# 14_Ethernet.net
KiCad netlist of a schematic drawn in Altium Designer
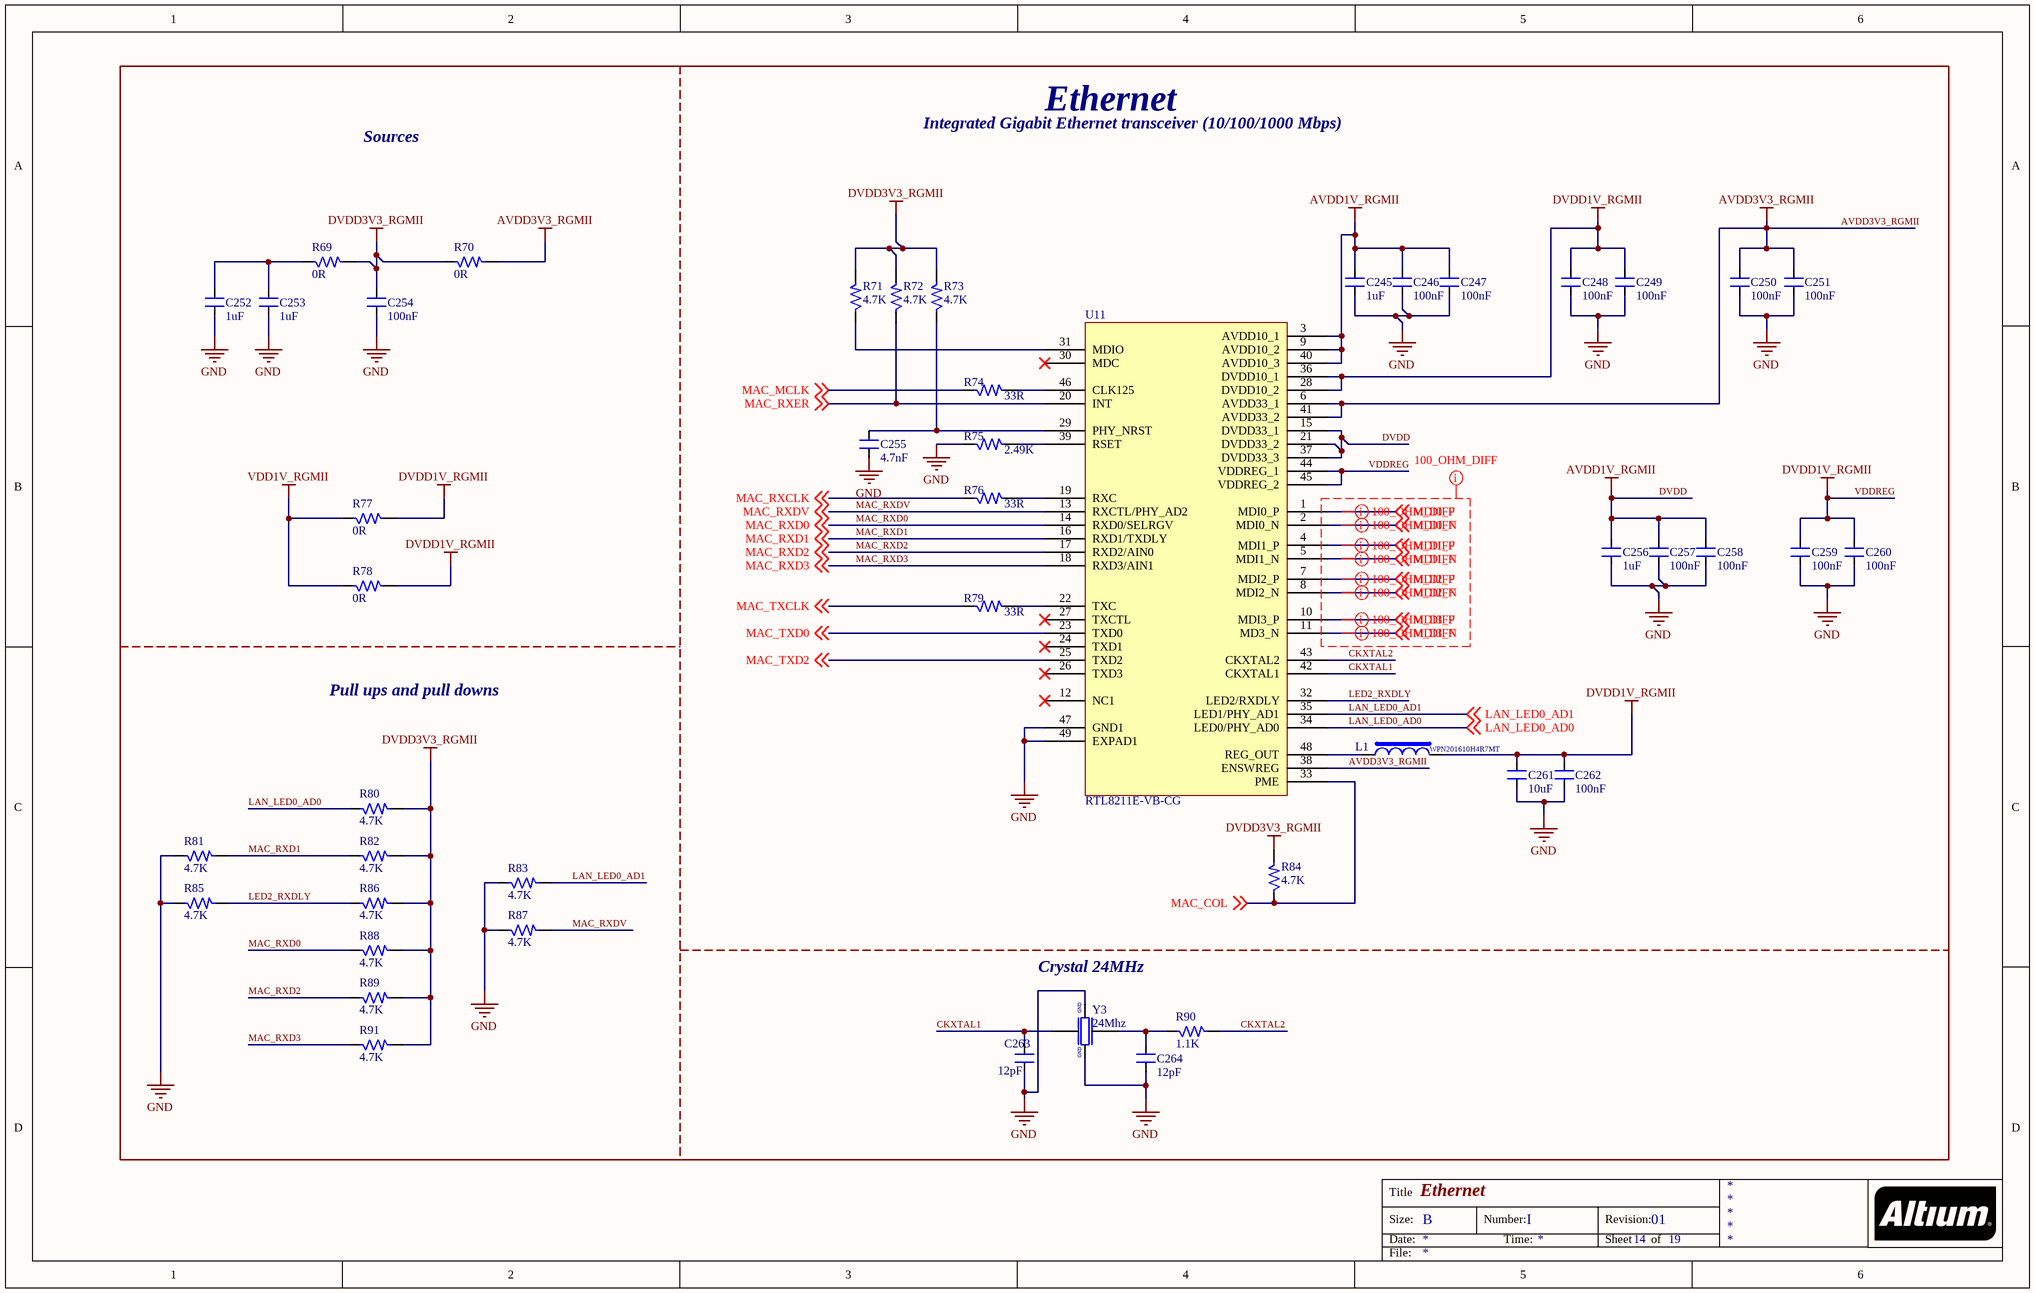
[diagram p0: [14] Ethernet.SchDoc]

(export (version "E")
  (design (tool "Eeschema 10.0.6"))
  (components
    (comp (ref "C245")
      (value "1uF")
      (footprint "CAP_0201")
      (description "1µF ±20% 16V Ceramic Capacitor X5R 0201 (0603 Metric)")
      (fields
        (field (name "MANUFACTURER") "Samsung Electro-Mechanics")
        (field (name "MANUFACTURER PART NUMBER") "CL03A105MO3NRNH")
      )
      (libsource (lib "EsteemPCB_SOM_Course_intlib") (part "CAP_1uF-16V-10%-0201"))
    )
    (comp (ref "C246")
      (value "100nF")
      (footprint "CAP_0201")
      (description "0.1µF ±10% 25V Ceramic Capacitor X5R 0201 (0603 Metric)")
      (fields
        (field (name "MANUFACTURER") "TDK Corporation")
        (field (name "MANUFACTURER PART NUMBER") "C0603X5R1E104K030BB")
      )
      (libsource (lib "EsteemPCB_SOM_Course_intlib") (part "CAP_100nF-25V-10%-0201"))
    )
    (comp (ref "C247")
      (value "100nF")
      (footprint "CAP_0201")
      (description "0.1µF ±10% 25V Ceramic Capacitor X5R 0201 (0603 Metric)")
      (fields
        (field (name "MANUFACTURER") "TDK Corporation")
        (field (name "MANUFACTURER PART NUMBER") "C0603X5R1E104K030BB")
      )
      (libsource (lib "EsteemPCB_SOM_Course_intlib") (part "CAP_100nF-25V-10%-0201"))
    )
    (comp (ref "C248")
      (value "100nF")
      (footprint "CAP_0201")
      (description "0.1µF ±10% 25V Ceramic Capacitor X5R 0201 (0603 Metric)")
      (fields
        (field (name "MANUFACTURER") "TDK Corporation")
        (field (name "MANUFACTURER PART NUMBER") "C0603X5R1E104K030BB")
      )
      (libsource (lib "EsteemPCB_SOM_Course_intlib") (part "CAP_100nF-25V-10%-0201"))
    )
    (comp (ref "C249")
      (value "100nF")
      (footprint "CAP_0201")
      (description "0.1µF ±10% 25V Ceramic Capacitor X5R 0201 (0603 Metric)")
      (fields
        (field (name "MANUFACTURER") "TDK Corporation")
        (field (name "MANUFACTURER PART NUMBER") "C0603X5R1E104K030BB")
      )
      (libsource (lib "EsteemPCB_SOM_Course_intlib") (part "CAP_100nF-25V-10%-0201"))
    )
    (comp (ref "C250")
      (value "100nF")
      (footprint "CAP_0201")
      (description "0.1µF ±10% 25V Ceramic Capacitor X5R 0201 (0603 Metric)")
      (fields
        (field (name "MANUFACTURER") "TDK Corporation")
        (field (name "MANUFACTURER PART NUMBER") "C0603X5R1E104K030BB")
      )
      (libsource (lib "EsteemPCB_SOM_Course_intlib") (part "CAP_100nF-25V-10%-0201"))
    )
    (comp (ref "C251")
      (value "100nF")
      (footprint "CAP_0201")
      (description "0.1µF ±10% 25V Ceramic Capacitor X5R 0201 (0603 Metric)")
      (fields
        (field (name "MANUFACTURER") "TDK Corporation")
        (field (name "MANUFACTURER PART NUMBER") "C0603X5R1E104K030BB")
      )
      (libsource (lib "EsteemPCB_SOM_Course_intlib") (part "CAP_100nF-25V-10%-0201"))
    )
    (comp (ref "C252")
      (value "1uF")
      (footprint "CAP_0402")
      (description "1µF ±10% 16V Ceramic Capacitor X5R 0402 (1005 Metric)")
      (fields
        (field (name "MANUFACTURER") "Knowles Novacap")
        (field (name "MANUFACTURER PART NUMBER") "0402BW105K160YT")
      )
      (libsource (lib "EsteemPCB_SOM_Course_intlib") (part "CAP_1uF-16V-10%-0402"))
    )
    (comp (ref "C253")
      (value "1uF")
      (footprint "CAP_0402")
      (description "1µF ±10% 16V Ceramic Capacitor X5R 0402 (1005 Metric)")
      (fields
        (field (name "MANUFACTURER") "Knowles Novacap")
        (field (name "MANUFACTURER PART NUMBER") "0402BW105K160YT")
      )
      (libsource (lib "EsteemPCB_SOM_Course_intlib") (part "CAP_1uF-16V-10%-0402"))
    )
    (comp (ref "C254")
      (value "100nF")
      (footprint "CAP_0201")
      (description "0.1µF ±10% 25V Ceramic Capacitor X5R 0201 (0603 Metric)")
      (fields
        (field (name "MANUFACTURER") "TDK Corporation")
        (field (name "MANUFACTURER PART NUMBER") "C0603X5R1E104K030BB")
      )
      (libsource (lib "EsteemPCB_SOM_Course_intlib") (part "CAP_100nF-25V-10%-0201"))
    )
    (comp (ref "C255")
      (value "4.7nF")
      (footprint "CAP_0201")
      (description "4700pF ±10% 10V Ceramic Capacitor X7R 0201 (0603 Metric)")
      (fields
        (field (name "MANUFACTURER") "AVX Corporation")
        (field (name "MANUFACTURER PART NUMBER") "0201ZC472KAT2A")
      )
      (libsource (lib "EsteemPCB_SOM_Course_intlib") (part "CAP_4.7nF-10V-10%-0201"))
    )
    (comp (ref "C256")
      (value "1uF")
      (footprint "CAP_0201")
      (description "1µF ±20% 16V Ceramic Capacitor X5R 0201 (0603 Metric)")
      (fields
        (field (name "MANUFACTURER") "Samsung Electro-Mechanics")
        (field (name "MANUFACTURER PART NUMBER") "CL03A105MO3NRNH")
      )
      (libsource (lib "EsteemPCB_SOM_Course_intlib") (part "CAP_1uF-16V-10%-0201"))
    )
    (comp (ref "C257")
      (value "100nF")
      (footprint "CAP_0201")
      (description "0.1µF ±10% 25V Ceramic Capacitor X5R 0201 (0603 Metric)")
      (fields
        (field (name "MANUFACTURER") "TDK Corporation")
        (field (name "MANUFACTURER PART NUMBER") "C0603X5R1E104K030BB")
      )
      (libsource (lib "EsteemPCB_SOM_Course_intlib") (part "CAP_100nF-25V-10%-0201"))
    )
    (comp (ref "C258")
      (value "100nF")
      (footprint "CAP_0201")
      (description "0.1µF ±10% 25V Ceramic Capacitor X5R 0201 (0603 Metric)")
      (fields
        (field (name "MANUFACTURER") "TDK Corporation")
        (field (name "MANUFACTURER PART NUMBER") "C0603X5R1E104K030BB")
      )
      (libsource (lib "EsteemPCB_SOM_Course_intlib") (part "CAP_100nF-25V-10%-0201"))
    )
    (comp (ref "C259")
      (value "100nF")
      (footprint "CAP_0201")
      (description "0.1µF ±10% 25V Ceramic Capacitor X5R 0201 (0603 Metric)")
      (fields
        (field (name "MANUFACTURER") "TDK Corporation")
        (field (name "MANUFACTURER PART NUMBER") "C0603X5R1E104K030BB")
      )
      (libsource (lib "EsteemPCB_SOM_Course_intlib") (part "CAP_100nF-25V-10%-0201"))
    )
    (comp (ref "C260")
      (value "100nF")
      (footprint "CAP_0201")
      (description "0.1µF ±10% 25V Ceramic Capacitor X5R 0201 (0603 Metric)")
      (fields
        (field (name "MANUFACTURER") "TDK Corporation")
        (field (name "MANUFACTURER PART NUMBER") "C0603X5R1E104K030BB")
      )
      (libsource (lib "EsteemPCB_SOM_Course_intlib") (part "CAP_100nF-25V-10%-0201"))
    )
    (comp (ref "C261")
      (value "10uF")
      (footprint "CAP_0402")
      (description "10µF ±20% 10V Ceramic Capacitor X5R 0402 (1005 Metric)")
      (fields
        (field (name "MANUFACTURER PART NUMBER") "CL05A106MP5NUNC")
        (field (name "MANUFACTURER") "Samsung Electro-Mechanics")
      )
      (libsource (lib "EsteemPCB_SOM_Course_intlib") (part "CAP_10uF-10V-20%-0402"))
    )
    (comp (ref "C262")
      (value "100nF")
      (footprint "CAP_0201")
      (description "0.1µF ±10% 25V Ceramic Capacitor X5R 0201 (0603 Metric)")
      (fields
        (field (name "MANUFACTURER") "TDK Corporation")
        (field (name "MANUFACTURER PART NUMBER") "C0603X5R1E104K030BB")
      )
      (libsource (lib "EsteemPCB_SOM_Course_intlib") (part "CAP_100nF-25V-10%-0201"))
    )
    (comp (ref "C263")
      (value "12pF")
      (footprint "CAP_0402")
      (description "12pF ±10% 10V Ceramic Capacitor X8R 0402 (1005 Metric)")
      (fields
        (field (name "MANUFACTURER") "KEMET")
        (field (name "MANUFACTURER PART NUMBER") "C0402C120K8HAC7867")
      )
      (libsource (lib "EsteemPCB_SOM_Course_intlib") (part "CAP_12pF-10V-10%-0402"))
    )
    (comp (ref "C264")
      (value "12pF")
      (footprint "CAP_0402")
      (description "12pF ±10% 10V Ceramic Capacitor X8R 0402 (1005 Metric)")
      (fields
        (field (name "MANUFACTURER") "KEMET")
        (field (name "MANUFACTURER PART NUMBER") "C0402C120K8HAC7867")
      )
      (libsource (lib "EsteemPCB_SOM_Course_intlib") (part "CAP_12pF-10V-10%-0402"))
    )
    (comp (ref "L1")
      (value "WPN201610H4R7MT")
      (footprint "IND_62.9_110X86.6_SMD")
      (description "4.7uH ±20% 900mA 425mΩ SMD,2.0x1.6x1.0mm Power Inductors RoHS")
      (fields (field (name "MANUFACTURER") "Sunlord"))
      (libsource (lib "EsteemPCB_SOM_Course_intlib") (part "IND_4.7uH-0.9A-20%-SMD"))
    )
    (comp (ref "R69")
      (value "0R")
      (footprint "RES_0201")
      (description "0 Ohms Jumper 0.05W, 1/20W Chip Resistor 0201 (0603 Metric) Automotive AEC-Q200 Thick Film")
      (fields
        (field (name "MANUFACTURER") "Bourns Inc.")
        (field (name "MANUFACTURER PART NUMBER") "CR0201AJ/-000GLF")
      )
      (libsource (lib "EsteemPCB_SOM_Course_intlib") (part "RES_0R-0.05W-1%-0201"))
    )
    (comp (ref "R70")
      (value "0R")
      (footprint "RES_0201")
      (description "0 Ohms Jumper 0.05W, 1/20W Chip Resistor 0201 (0603 Metric) Automotive AEC-Q200 Thick Film")
      (fields
        (field (name "MANUFACTURER") "Bourns Inc.")
        (field (name "MANUFACTURER PART NUMBER") "CR0201AJ/-000GLF")
      )
      (libsource (lib "EsteemPCB_SOM_Course_intlib") (part "RES_0R-0.05W-1%-0201"))
    )
    (comp (ref "R71")
      (value "4.7K")
      (footprint "RES_0201")
      (description "4.02 kOhms ±1% 0.05W, 1/20W Chip Resistor 0201 (0603 Metric) Thick Film")
      (fields
        (field (name "MANUFACTURER") "Yageo")
        (field (name "MANUFACTURER PART NUMBER") "RC0201FR-074K02L")
      )
      (libsource (lib "EsteemPCB_SOM_Course_intlib") (part "RES_4.7K-0.1W-1%-0201"))
    )
    (comp (ref "R72")
      (value "4.7K")
      (footprint "RES_0201")
      (description "4.02 kOhms ±1% 0.05W, 1/20W Chip Resistor 0201 (0603 Metric) Thick Film")
      (fields
        (field (name "MANUFACTURER") "Yageo")
        (field (name "MANUFACTURER PART NUMBER") "RC0201FR-074K02L")
      )
      (libsource (lib "EsteemPCB_SOM_Course_intlib") (part "RES_4.7K-0.1W-1%-0201"))
    )
    (comp (ref "R73")
      (value "4.7K")
      (footprint "RES_0201")
      (description "4.02 kOhms ±1% 0.05W, 1/20W Chip Resistor 0201 (0603 Metric) Thick Film")
      (fields
        (field (name "MANUFACTURER") "Yageo")
        (field (name "MANUFACTURER PART NUMBER") "RC0201FR-074K02L")
      )
      (libsource (lib "EsteemPCB_SOM_Course_intlib") (part "RES_4.7K-0.1W-1%-0201"))
    )
    (comp (ref "R74")
      (value "33R")
      (footprint "RES_0201")
      (description "33 Ohms ±1% 0.05W, 1/20W Chip Resistor 0201 (0603 Metric) Thick Film")
      (fields
        (field (name "MANUFACTURER") "Yageo")
        (field (name "MANUFACTURER PART NUMBER") "RC0201FR-0733RL")
      )
      (libsource (lib "EsteemPCB_SOM_Course_intlib") (part "RES_33R-0.05W-1%-0201"))
    )
    (comp (ref "R75")
      (value "2.49K")
      (footprint "RES_0201")
      (description "2.49 kOhms ±1% 0.05W, 1/20W Chip Resistor 0201 (0603 Metric) Automotive AEC-Q200 Thick Film")
      (fields
        (field (name "MANUFACTURER") "Panasonic Electronic Components")
        (field (name "MANUFACTURER PART NUMBER") "ERJ-1GNF2491C")
      )
      (libsource (lib "EsteemPCB_SOM_Course_intlib") (part "RES_2.49K-0.05W-1%-0201"))
    )
    (comp (ref "R76")
      (value "33R")
      (footprint "RES_0201")
      (description "33 Ohms ±1% 0.05W, 1/20W Chip Resistor 0201 (0603 Metric) Thick Film")
      (fields
        (field (name "MANUFACTURER") "Yageo")
        (field (name "MANUFACTURER PART NUMBER") "RC0201FR-0733RL")
      )
      (libsource (lib "EsteemPCB_SOM_Course_intlib") (part "RES_33R-0.05W-1%-0201"))
    )
    (comp (ref "R77")
      (value "0R")
      (footprint "RES_0201")
      (description "0 Ohms Jumper 0.05W, 1/20W Chip Resistor 0201 (0603 Metric) Automotive AEC-Q200 Thick Film")
      (fields
        (field (name "MANUFACTURER") "Bourns Inc.")
        (field (name "MANUFACTURER PART NUMBER") "CR0201AJ/-000GLF")
      )
      (libsource (lib "EsteemPCB_SOM_Course_intlib") (part "RES_0R-0.05W-1%-0201"))
    )
    (comp (ref "R78")
      (value "0R")
      (footprint "RES_0201")
      (description "0 Ohms Jumper 0.05W, 1/20W Chip Resistor 0201 (0603 Metric) Automotive AEC-Q200 Thick Film")
      (fields
        (field (name "MANUFACTURER") "Bourns Inc.")
        (field (name "MANUFACTURER PART NUMBER") "CR0201AJ/-000GLF")
      )
      (libsource (lib "EsteemPCB_SOM_Course_intlib") (part "RES_0R-0.05W-1%-0201"))
    )
    (comp (ref "R79")
      (value "33R")
      (footprint "RES_0201")
      (description "33 Ohms ±1% 0.05W, 1/20W Chip Resistor 0201 (0603 Metric) Thick Film")
      (fields
        (field (name "MANUFACTURER") "Yageo")
        (field (name "MANUFACTURER PART NUMBER") "RC0201FR-0733RL")
      )
      (libsource (lib "EsteemPCB_SOM_Course_intlib") (part "RES_33R-0.05W-1%-0201"))
    )
    (comp (ref "R80")
      (value "4.7K")
      (footprint "RES_0201")
      (description "4.02 kOhms ±1% 0.05W, 1/20W Chip Resistor 0201 (0603 Metric) Thick Film")
      (fields
        (field (name "MANUFACTURER") "Yageo")
        (field (name "MANUFACTURER PART NUMBER") "RC0201FR-074K02L")
      )
      (libsource (lib "EsteemPCB_SOM_Course_intlib") (part "RES_4.7K-0.1W-1%-0201"))
    )
    (comp (ref "R81")
      (value "4.7K")
      (footprint "RES_0201")
      (description "4.02 kOhms ±1% 0.05W, 1/20W Chip Resistor 0201 (0603 Metric) Thick Film")
      (fields
        (field (name "MANUFACTURER") "Yageo")
        (field (name "MANUFACTURER PART NUMBER") "RC0201FR-074K02L")
      )
      (libsource (lib "EsteemPCB_SOM_Course_intlib") (part "RES_4.7K-0.1W-1%-0201"))
    )
    (comp (ref "R82")
      (value "4.7K")
      (footprint "RES_0201")
      (description "4.02 kOhms ±1% 0.05W, 1/20W Chip Resistor 0201 (0603 Metric) Thick Film")
      (fields
        (field (name "MANUFACTURER") "Yageo")
        (field (name "MANUFACTURER PART NUMBER") "RC0201FR-074K02L")
      )
      (libsource (lib "EsteemPCB_SOM_Course_intlib") (part "RES_4.7K-0.1W-1%-0201"))
    )
    (comp (ref "R83")
      (value "4.7K")
      (footprint "RES_0201")
      (description "4.02 kOhms ±1% 0.05W, 1/20W Chip Resistor 0201 (0603 Metric) Thick Film")
      (fields
        (field (name "MANUFACTURER") "Yageo")
        (field (name "MANUFACTURER PART NUMBER") "RC0201FR-074K02L")
      )
      (libsource (lib "EsteemPCB_SOM_Course_intlib") (part "RES_4.7K-0.1W-1%-0201"))
    )
    (comp (ref "R84")
      (value "4.7K")
      (footprint "RES_0201")
      (description "4.02 kOhms ±1% 0.05W, 1/20W Chip Resistor 0201 (0603 Metric) Thick Film")
      (fields
        (field (name "MANUFACTURER") "Yageo")
        (field (name "MANUFACTURER PART NUMBER") "RC0201FR-074K02L")
      )
      (libsource (lib "EsteemPCB_SOM_Course_intlib") (part "RES_4.7K-0.1W-1%-0201"))
    )
    (comp (ref "R85")
      (value "4.7K")
      (footprint "RES_0201")
      (description "4.02 kOhms ±1% 0.05W, 1/20W Chip Resistor 0201 (0603 Metric) Thick Film")
      (fields
        (field (name "MANUFACTURER") "Yageo")
        (field (name "MANUFACTURER PART NUMBER") "RC0201FR-074K02L")
      )
      (libsource (lib "EsteemPCB_SOM_Course_intlib") (part "RES_4.7K-0.1W-1%-0201"))
    )
    (comp (ref "R86")
      (value "4.7K")
      (footprint "RES_0201")
      (description "4.02 kOhms ±1% 0.05W, 1/20W Chip Resistor 0201 (0603 Metric) Thick Film")
      (fields
        (field (name "MANUFACTURER") "Yageo")
        (field (name "MANUFACTURER PART NUMBER") "RC0201FR-074K02L")
      )
      (libsource (lib "EsteemPCB_SOM_Course_intlib") (part "RES_4.7K-0.1W-1%-0201"))
    )
    (comp (ref "R87")
      (value "4.7K")
      (footprint "RES_0201")
      (description "4.02 kOhms ±1% 0.05W, 1/20W Chip Resistor 0201 (0603 Metric) Thick Film")
      (fields
        (field (name "MANUFACTURER") "Yageo")
        (field (name "MANUFACTURER PART NUMBER") "RC0201FR-074K02L")
      )
      (libsource (lib "EsteemPCB_SOM_Course_intlib") (part "RES_4.7K-0.1W-1%-0201"))
    )
    (comp (ref "R88")
      (value "4.7K")
      (footprint "RES_0201")
      (description "4.02 kOhms ±1% 0.05W, 1/20W Chip Resistor 0201 (0603 Metric) Thick Film")
      (fields
        (field (name "MANUFACTURER") "Yageo")
        (field (name "MANUFACTURER PART NUMBER") "RC0201FR-074K02L")
      )
      (libsource (lib "EsteemPCB_SOM_Course_intlib") (part "RES_4.7K-0.1W-1%-0201"))
    )
    (comp (ref "R89")
      (value "4.7K")
      (footprint "RES_0201")
      (description "4.02 kOhms ±1% 0.05W, 1/20W Chip Resistor 0201 (0603 Metric) Thick Film")
      (fields
        (field (name "MANUFACTURER") "Yageo")
        (field (name "MANUFACTURER PART NUMBER") "RC0201FR-074K02L")
      )
      (libsource (lib "EsteemPCB_SOM_Course_intlib") (part "RES_4.7K-0.1W-1%-0201"))
    )
    (comp (ref "R90")
      (value "1.1K")
      (footprint "RES_0201")
      (description "1.1 kOhms ±1% 0.05W, 1/20W Chip Resistor 0201 (0603 Metric) Automotive AEC-Q200 Thick Film")
      (fields
        (field (name "MANUFACTURER") "Panasonic Electronic Components")
        (field (name "MANUFACTURER PART NUMBER") "ERJ-1GNF1101C")
      )
      (libsource (lib "EsteemPCB_SOM_Course_intlib") (part "RES_1.1K-0.05W-1%-0201"))
    )
    (comp (ref "R91")
      (value "4.7K")
      (footprint "RES_0201")
      (description "4.02 kOhms ±1% 0.05W, 1/20W Chip Resistor 0201 (0603 Metric) Thick Film")
      (fields
        (field (name "MANUFACTURER") "Yageo")
        (field (name "MANUFACTURER PART NUMBER") "RC0201FR-074K02L")
      )
      (libsource (lib "EsteemPCB_SOM_Course_intlib") (part "RES_4.7K-0.1W-1%-0201"))
    )
    (comp (ref "U11")
      (value "RTL8211E-VB-CG")
      (footprint "QFN48_19.6_324X324_SMD")
      (fields (field (name "MANUFACTURER") "Realtek Semicon"))
      (libsource (lib "EsteemPCB_SOM_Course_intlib") (part "IC_RTL8211E-VB-CG"))
    )
    (comp (ref "Y3")
      (value "24Mhz")
      (footprint "XTAL_ABM8AIG-24.000MHZ-12-2Z-T3")
      (description "24MHz ±20ppm Crystal 12pF 50 Ohms 4-SMD, No Lead")
      (fields
        (field (name "MANUFACTURER") "Abracon LLC")
        (field (name "MANUFACTURER PART NUMBER") "ABM8AIG-24.000MHZ-12-2Z-T3")
      )
      (libsource (lib "EsteemPCB_SOM_Course_intlib") (part "XTAL_24Mhz-12pF-4-SMD"))
    )
  )
  (nets
    (net (code "1") (name "/CKXTAL1") (class "Default")
      (node (ref "C263") (pin "2") (pinfunction "2_2") (pintype "passive"))
      (node (ref "U11") (pin "42") (pinfunction "CKXTAL1_42") (pintype "passive"))
      (node (ref "Y3") (pin "1") (pinfunction "1_1") (pintype "passive"))
    )
    (net (code "2") (name "/CKXTAL2") (class "Default")
      (node (ref "R90") (pin "2") (pinfunction "2_2") (pintype "passive"))
      (node (ref "U11") (pin "43") (pinfunction "CKXTAL2_43") (pintype "passive"))
    )
    (net (code "3") (name "/LED2_RXDLY") (class "Default")
      (node (ref "R85") (pin "2") (pinfunction "2_2") (pintype "passive"))
      (node (ref "R86") (pin "1") (pinfunction "1_1") (pintype "passive"))
      (node (ref "U11") (pin "32") (pinfunction "LED2/RXDLY_32") (pintype "passive"))
    )
    (net (code "4") (name "AVDD1V_RGMII") (class "Default")
      (node (ref "C245") (pin "2") (pinfunction "2_2") (pintype "passive"))
      (node (ref "C246") (pin "2") (pinfunction "2_2") (pintype "passive"))
      (node (ref "C247") (pin "2") (pinfunction "2_2") (pintype "passive"))
      (node (ref "C256") (pin "2") (pinfunction "2_2") (pintype "passive"))
      (node (ref "C257") (pin "2") (pinfunction "2_2") (pintype "passive"))
      (node (ref "C258") (pin "2") (pinfunction "2_2") (pintype "passive"))
      (node (ref "U11") (pin "15") (pinfunction "DVDD33_1_15") (pintype "passive"))
      (node (ref "U11") (pin "21") (pinfunction "DVDD33_2_21") (pintype "passive"))
      (node (ref "U11") (pin "3") (pinfunction "AVDD10_1_3") (pintype "passive"))
      (node (ref "U11") (pin "37") (pinfunction "DVDD33_3_37") (pintype "passive"))
      (node (ref "U11") (pin "40") (pinfunction "AVDD10_3_40") (pintype "passive"))
      (node (ref "U11") (pin "9") (pinfunction "AVDD10_2_9") (pintype "passive"))
    )
    (net (code "5") (name "AVDD3V3_RGMII") (class "Default")
      (node (ref "C250") (pin "2") (pinfunction "2_2") (pintype "passive"))
      (node (ref "C251") (pin "2") (pinfunction "2_2") (pintype "passive"))
      (node (ref "R70") (pin "2") (pinfunction "2_2") (pintype "passive"))
      (node (ref "U11") (pin "38") (pinfunction "ENSWREG_38") (pintype "passive"))
      (node (ref "U11") (pin "41") (pinfunction "AVDD33_2_41") (pintype "passive"))
      (node (ref "U11") (pin "6") (pinfunction "AVDD33_1_6") (pintype "passive"))
    )
    (net (code "6") (name "DVDD1V_RGMII") (class "Default")
      (node (ref "C248") (pin "2") (pinfunction "2_2") (pintype "passive"))
      (node (ref "C249") (pin "2") (pinfunction "2_2") (pintype "passive"))
      (node (ref "C259") (pin "2") (pinfunction "2_2") (pintype "passive"))
      (node (ref "C260") (pin "2") (pinfunction "2_2") (pintype "passive"))
      (node (ref "C261") (pin "2") (pinfunction "2_2") (pintype "passive"))
      (node (ref "C262") (pin "2") (pinfunction "2_2") (pintype "passive"))
      (node (ref "L1") (pin "2") (pinfunction "2_2") (pintype "passive"))
      (node (ref "R77") (pin "2") (pinfunction "2_2") (pintype "passive"))
      (node (ref "R78") (pin "2") (pinfunction "2_2") (pintype "passive"))
      (node (ref "U11") (pin "28") (pinfunction "DVDD10_2_28") (pintype "passive"))
      (node (ref "U11") (pin "36") (pinfunction "DVDD10_1_36") (pintype "passive"))
      (node (ref "U11") (pin "44") (pinfunction "VDDREG_1_44") (pintype "passive"))
      (node (ref "U11") (pin "45") (pinfunction "VDDREG_2_45") (pintype "passive"))
    )
    (net (code "7") (name "DVDD3V3_RGMII") (class "Default")
      (node (ref "C254") (pin "2") (pinfunction "2_2") (pintype "passive"))
      (node (ref "R69") (pin "2") (pinfunction "2_2") (pintype "passive"))
      (node (ref "R70") (pin "1") (pinfunction "1_1") (pintype "passive"))
      (node (ref "R71") (pin "2") (pinfunction "2_2") (pintype "passive"))
      (node (ref "R72") (pin "2") (pinfunction "2_2") (pintype "passive"))
      (node (ref "R73") (pin "2") (pinfunction "2_2") (pintype "passive"))
      (node (ref "R80") (pin "2") (pinfunction "2_2") (pintype "passive"))
      (node (ref "R82") (pin "2") (pinfunction "2_2") (pintype "passive"))
      (node (ref "R84") (pin "2") (pinfunction "2_2") (pintype "passive"))
      (node (ref "R86") (pin "2") (pinfunction "2_2") (pintype "passive"))
      (node (ref "R88") (pin "2") (pinfunction "2_2") (pintype "passive"))
      (node (ref "R89") (pin "2") (pinfunction "2_2") (pintype "passive"))
      (node (ref "R91") (pin "2") (pinfunction "2_2") (pintype "passive"))
    )
    (net (code "8") (name "GND") (class "Default")
      (node (ref "C245") (pin "1") (pinfunction "1_1") (pintype "passive"))
      (node (ref "C246") (pin "1") (pinfunction "1_1") (pintype "passive"))
      (node (ref "C247") (pin "1") (pinfunction "1_1") (pintype "passive"))
      (node (ref "C248") (pin "1") (pinfunction "1_1") (pintype "passive"))
      (node (ref "C249") (pin "1") (pinfunction "1_1") (pintype "passive"))
      (node (ref "C250") (pin "1") (pinfunction "1_1") (pintype "passive"))
      (node (ref "C251") (pin "1") (pinfunction "1_1") (pintype "passive"))
      (node (ref "C252") (pin "1") (pinfunction "1_1") (pintype "passive"))
      (node (ref "C253") (pin "1") (pinfunction "1_1") (pintype "passive"))
      (node (ref "C254") (pin "1") (pinfunction "1_1") (pintype "passive"))
      (node (ref "C255") (pin "1") (pinfunction "1_1") (pintype "passive"))
      (node (ref "C256") (pin "1") (pinfunction "1_1") (pintype "passive"))
      (node (ref "C257") (pin "1") (pinfunction "1_1") (pintype "passive"))
      (node (ref "C258") (pin "1") (pinfunction "1_1") (pintype "passive"))
      (node (ref "C259") (pin "1") (pinfunction "1_1") (pintype "passive"))
      (node (ref "C260") (pin "1") (pinfunction "1_1") (pintype "passive"))
      (node (ref "C261") (pin "1") (pinfunction "1_1") (pintype "passive"))
      (node (ref "C262") (pin "1") (pinfunction "1_1") (pintype "passive"))
      (node (ref "C263") (pin "1") (pinfunction "1_1") (pintype "passive"))
      (node (ref "C264") (pin "1") (pinfunction "1_1") (pintype "passive"))
      (node (ref "R75") (pin "1") (pinfunction "1_1") (pintype "passive"))
      (node (ref "R81") (pin "1") (pinfunction "1_1") (pintype "passive"))
      (node (ref "R83") (pin "1") (pinfunction "1_1") (pintype "passive"))
      (node (ref "R85") (pin "1") (pinfunction "1_1") (pintype "passive"))
      (node (ref "R87") (pin "1") (pinfunction "1_1") (pintype "passive"))
      (node (ref "U11") (pin "47") (pinfunction "GND1_47") (pintype "passive"))
      (node (ref "U11") (pin "49") (pinfunction "EXPAD1_49") (pintype "passive"))
      (node (ref "Y3") (pin "2") (pinfunction "2_2") (pintype "passive"))
      (node (ref "Y3") (pin "4") (pinfunction "4_4") (pintype "passive"))
    )
    (net (code "9") (name "LAN_LED0_AD0") (class "Default")
      (node (ref "R80") (pin "1") (pinfunction "1_1") (pintype "passive"))
      (node (ref "U11") (pin "34") (pinfunction "LED0/PHY_AD0_34") (pintype "passive"))
    )
    (net (code "10") (name "LAN_LED0_AD1") (class "Default")
      (node (ref "R83") (pin "2") (pinfunction "2_2") (pintype "passive"))
      (node (ref "U11") (pin "35") (pinfunction "LED1/PHY_AD1_35") (pintype "passive"))
    )
    (net (code "11") (name "MAC_COL") (class "Default")
      (node (ref "R84") (pin "1") (pinfunction "1_1") (pintype "passive"))
      (node (ref "U11") (pin "33") (pinfunction "PME_33") (pintype "passive"))
    )
    (net (code "12") (name "MAC_MCLK") (class "Default")
      (node (ref "R74") (pin "1") (pinfunction "1_1") (pintype "passive"))
    )
    (net (code "13") (name "MAC_RXCLK") (class "Default")
      (node (ref "R76") (pin "1") (pinfunction "1_1") (pintype "passive"))
    )
    (net (code "14") (name "MAC_RXD0") (class "Default")
      (node (ref "R88") (pin "1") (pinfunction "1_1") (pintype "passive"))
      (node (ref "U11") (pin "14") (pinfunction "RXD0/SELRGV_14") (pintype "passive"))
    )
    (net (code "15") (name "MAC_RXD1") (class "Default")
      (node (ref "R81") (pin "2") (pinfunction "2_2") (pintype "passive"))
      (node (ref "R82") (pin "1") (pinfunction "1_1") (pintype "passive"))
      (node (ref "U11") (pin "16") (pinfunction "RXD1/TXDLY_16") (pintype "passive"))
    )
    (net (code "16") (name "MAC_RXD2") (class "Default")
      (node (ref "R89") (pin "1") (pinfunction "1_1") (pintype "passive"))
      (node (ref "U11") (pin "17") (pinfunction "RXD2/AIN0_17") (pintype "passive"))
    )
    (net (code "17") (name "MAC_RXD3") (class "Default")
      (node (ref "R91") (pin "1") (pinfunction "1_1") (pintype "passive"))
      (node (ref "U11") (pin "18") (pinfunction "RXD3/AIN1_18") (pintype "passive"))
    )
    (net (code "18") (name "MAC_RXDV") (class "Default")
      (node (ref "R87") (pin "2") (pinfunction "2_2") (pintype "passive"))
      (node (ref "U11") (pin "13") (pinfunction "RXCTL/PHY_AD2_13") (pintype "passive"))
    )
    (net (code "19") (name "MAC_RXER") (class "Default")
      (node (ref "R72") (pin "1") (pinfunction "1_1") (pintype "passive"))
      (node (ref "U11") (pin "20") (pinfunction "INT_20") (pintype "passive"))
    )
    (net (code "20") (name "MAC_TXCLK") (class "Default")
      (node (ref "R79") (pin "1") (pinfunction "1_1") (pintype "passive"))
    )
    (net (code "21") (name "MAC_TXD0") (class "Default")
      (node (ref "U11") (pin "23") (pinfunction "TXD0_23") (pintype "passive"))
    )
    (net (code "22") (name "MAC_TXD2") (class "Default")
      (node (ref "U11") (pin "25") (pinfunction "TXD2_25") (pintype "passive"))
    )
    (net (code "23") (name "MDI0_N") (class "Default")
      (node (ref "U11") (pin "2") (pinfunction "MDI0_N_2") (pintype "passive"))
    )
    (net (code "24") (name "MDI0_P") (class "Default")
      (node (ref "U11") (pin "1") (pinfunction "MDI0_P_1") (pintype "passive"))
    )
    (net (code "25") (name "MDI1_N") (class "Default")
      (node (ref "U11") (pin "5") (pinfunction "MDI1_N_5") (pintype "passive"))
    )
    (net (code "26") (name "MDI1_P") (class "Default")
      (node (ref "U11") (pin "4") (pinfunction "MDI1_P_4") (pintype "passive"))
    )
    (net (code "27") (name "MDI2_N") (class "Default")
      (node (ref "U11") (pin "8") (pinfunction "MDI2_N_8") (pintype "passive"))
    )
    (net (code "28") (name "MDI2_P") (class "Default")
      (node (ref "U11") (pin "7") (pinfunction "MDI2_P_7") (pintype "passive"))
    )
    (net (code "29") (name "MDI3_N") (class "Default")
      (node (ref "U11") (pin "11") (pinfunction "MD3_N_11") (pintype "passive"))
    )
    (net (code "30") (name "MDI3_P") (class "Default")
      (node (ref "U11") (pin "10") (pinfunction "MDI3_P_10") (pintype "passive"))
    )
    (net (code "31") (name "Net-(C252-Pad2)") (class "Default")
      (node (ref "C252") (pin "2") (pinfunction "2_2") (pintype "passive"))
      (node (ref "C253") (pin "2") (pinfunction "2_2") (pintype "passive"))
      (node (ref "R69") (pin "1") (pinfunction "1_1") (pintype "passive"))
    )
    (net (code "32") (name "Net-(C264-Pad2)") (class "Default")
      (node (ref "C264") (pin "2") (pinfunction "2_2") (pintype "passive"))
      (node (ref "R90") (pin "1") (pinfunction "1_1") (pintype "passive"))
      (node (ref "Y3") (pin "3") (pinfunction "3_3") (pintype "passive"))
    )
    (net (code "33") (name "Net-(U11-CLK125)") (class "Default")
      (node (ref "R74") (pin "2") (pinfunction "2_2") (pintype "passive"))
      (node (ref "U11") (pin "46") (pinfunction "CLK125_46") (pintype "passive"))
    )
    (net (code "34") (name "Net-(U11-MDIO)") (class "Default")
      (node (ref "R71") (pin "1") (pinfunction "1_1") (pintype "passive"))
      (node (ref "U11") (pin "31") (pinfunction "MDIO_31") (pintype "passive"))
    )
    (net (code "35") (name "Net-(U11-PHY_NRST)") (class "Default")
      (node (ref "C255") (pin "2") (pinfunction "2_2") (pintype "passive"))
      (node (ref "R73") (pin "1") (pinfunction "1_1") (pintype "passive"))
      (node (ref "U11") (pin "29") (pinfunction "PHY_NRST_29") (pintype "passive"))
    )
    (net (code "36") (name "Net-(U11-REG_OUT)") (class "Default")
      (node (ref "L1") (pin "1") (pinfunction "1_1") (pintype "passive"))
      (node (ref "U11") (pin "48") (pinfunction "REG_OUT_48") (pintype "passive"))
    )
    (net (code "37") (name "Net-(U11-RSET)") (class "Default")
      (node (ref "R75") (pin "2") (pinfunction "2_2") (pintype "passive"))
      (node (ref "U11") (pin "39") (pinfunction "RSET_39") (pintype "passive"))
    )
    (net (code "38") (name "Net-(U11-RXC)") (class "Default")
      (node (ref "R76") (pin "2") (pinfunction "2_2") (pintype "passive"))
      (node (ref "U11") (pin "19") (pinfunction "RXC_19") (pintype "passive"))
    )
    (net (code "39") (name "Net-(U11-TXC)") (class "Default")
      (node (ref "R79") (pin "2") (pinfunction "2_2") (pintype "passive"))
      (node (ref "U11") (pin "22") (pinfunction "TXC_22") (pintype "passive"))
    )
    (net (code "40") (name "VDD1V_RGMII") (class "Default")
      (node (ref "R77") (pin "1") (pinfunction "1_1") (pintype "passive"))
      (node (ref "R78") (pin "1") (pinfunction "1_1") (pintype "passive"))
    )
    (net (code "41") (name "unconnected-(U11-MDC-Pad30)") (class "Default")
      (node (ref "U11") (pin "30") (pinfunction "MDC_30") (pintype "passive+no_connect"))
    )
    (net (code "42") (name "unconnected-(U11-NC1-Pad12)") (class "Default")
      (node (ref "U11") (pin "12") (pinfunction "NC1_12") (pintype "passive+no_connect"))
    )
    (net (code "43") (name "unconnected-(U11-TXCTL-Pad27)") (class "Default")
      (node (ref "U11") (pin "27") (pinfunction "TXCTL_27") (pintype "passive+no_connect"))
    )
    (net (code "44") (name "unconnected-(U11-TXD1-Pad24)") (class "Default")
      (node (ref "U11") (pin "24") (pinfunction "TXD1_24") (pintype "passive+no_connect"))
    )
    (net (code "45") (name "unconnected-(U11-TXD3-Pad26)") (class "Default")
      (node (ref "U11") (pin "26") (pinfunction "TXD3_26") (pintype "passive+no_connect"))
    )
  )
)
